# LVDS_IFC_DAC.net
KiCad netlist of a schematic drawn in Altium Designer
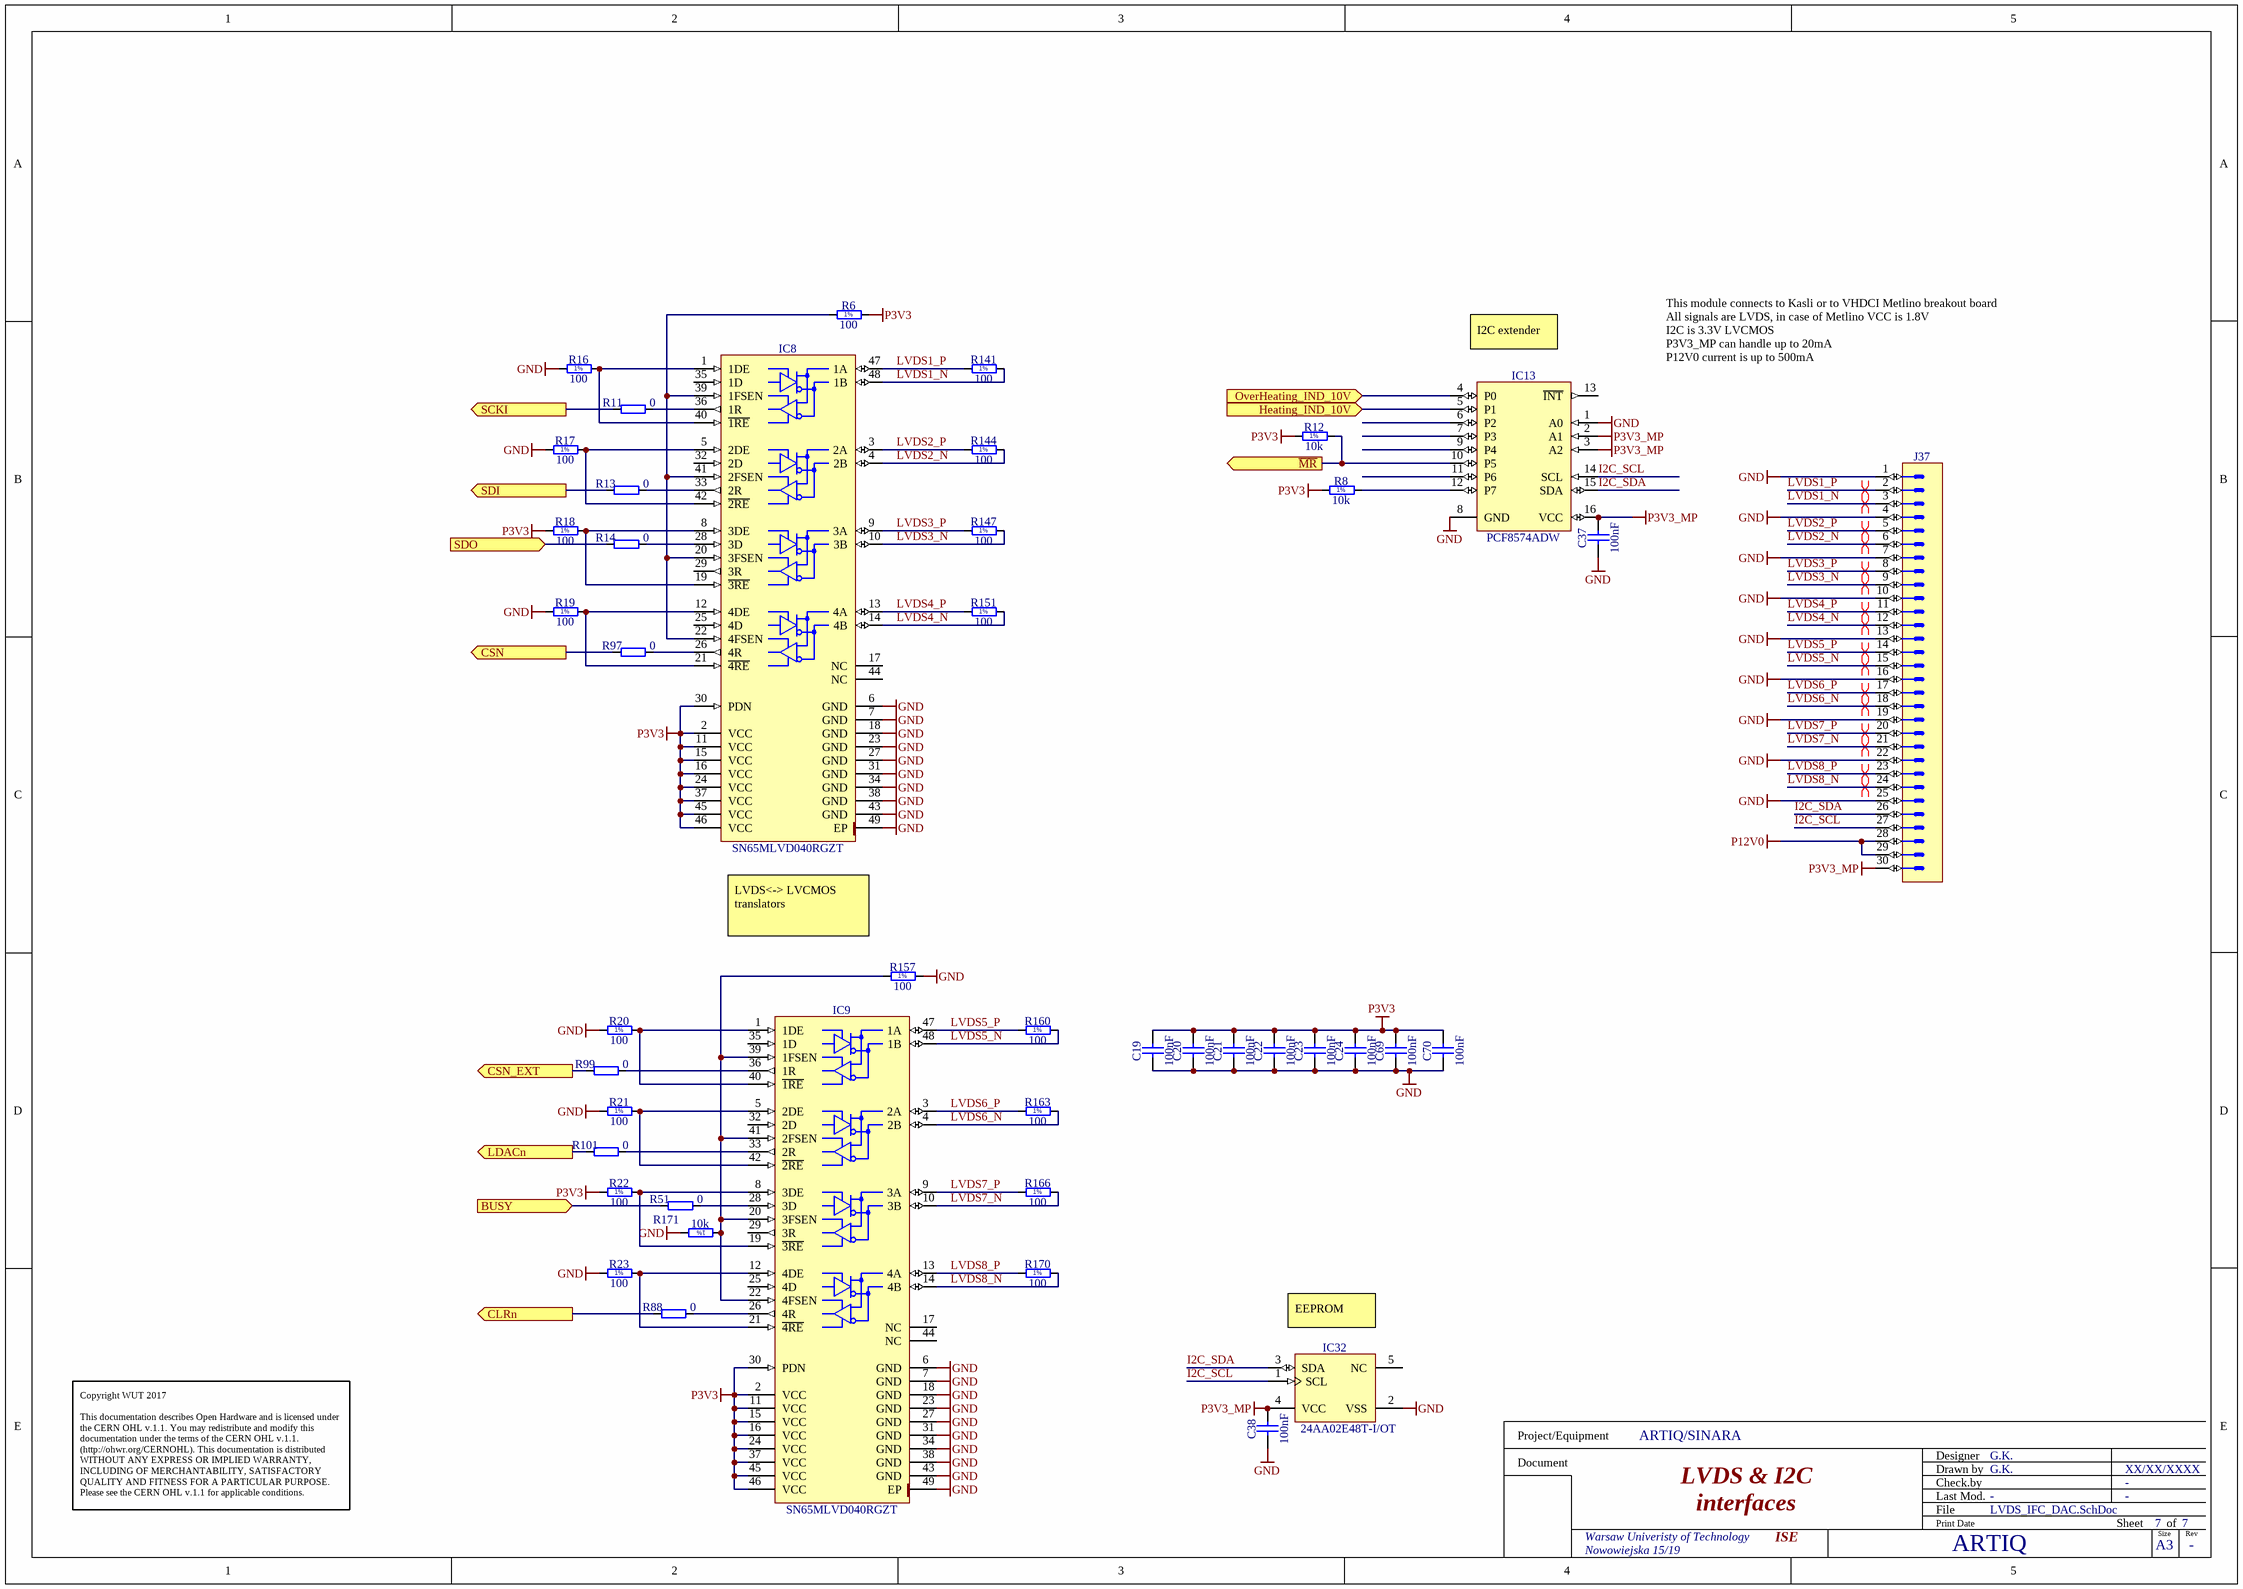
[diagram p0: LVDS_IFC_DAC.SchDoc]

(export (version "E")
  (design (tool "Eeschema 10.0.6"))
  (components
    (comp (ref "C19")
      (value "100nF")
      (footprint "CAPC1005X55N")
      (description "Non-polarised capacitor")
      (fields
        (field (name "PART NUMBER") "CC0402_100NF_16V_10%_X5R")
        (field (name "VOLTAGE") "16V")
        (field (name "AUTHOR") "CERN DEM JLC")
      )
      (libsource (lib "Capacitors") (part "Capacitor - non polarized"))
    )
    (comp (ref "C20")
      (value "100nF")
      (footprint "CAPC1005X55N")
      (description "Non-polarised capacitor")
      (fields
        (field (name "PART NUMBER") "CC0402_100NF_16V_10%_X5R")
        (field (name "VOLTAGE") "16V")
        (field (name "AUTHOR") "CERN DEM JLC")
      )
      (libsource (lib "Capacitors") (part "Capacitor - non polarized"))
    )
    (comp (ref "C21")
      (value "100nF")
      (footprint "CAPC1005X55N")
      (description "Non-polarised capacitor")
      (fields
        (field (name "PART NUMBER") "CC0402_100NF_16V_10%_X5R")
        (field (name "VOLTAGE") "16V")
        (field (name "AUTHOR") "CERN DEM JLC")
      )
      (libsource (lib "Capacitors") (part "Capacitor - non polarized"))
    )
    (comp (ref "C22")
      (value "100nF")
      (footprint "CAPC1005X55N")
      (description "Non-polarised capacitor")
      (fields
        (field (name "PART NUMBER") "CC0402_100NF_16V_10%_X5R")
        (field (name "VOLTAGE") "16V")
        (field (name "AUTHOR") "CERN DEM JLC")
      )
      (libsource (lib "Capacitors") (part "Capacitor - non polarized"))
    )
    (comp (ref "C23")
      (value "100nF")
      (footprint "CAPC1005X55N")
      (description "Non-polarised capacitor")
      (fields
        (field (name "PART NUMBER") "CC0402_100NF_16V_10%_X5R")
        (field (name "VOLTAGE") "16V")
        (field (name "AUTHOR") "CERN DEM JLC")
      )
      (libsource (lib "Capacitors") (part "Capacitor - non polarized"))
    )
    (comp (ref "C24")
      (value "100nF")
      (footprint "CAPC1005X55N")
      (description "Non-polarised capacitor")
      (fields
        (field (name "PART NUMBER") "CC0402_100NF_16V_10%_X5R")
        (field (name "VOLTAGE") "16V")
        (field (name "AUTHOR") "CERN DEM JLC")
      )
      (libsource (lib "Capacitors") (part "Capacitor - non polarized"))
    )
    (comp (ref "C37")
      (value "100nF")
      (footprint "CAPC1005X55N")
      (description "Non-polarised capacitor")
      (fields
        (field (name "PART NUMBER") "CC0402_100NF_16V_10%_X5R")
        (field (name "VOLTAGE") "16V")
        (field (name "AUTHOR") "CERN DEM JLC")
      )
      (libsource (lib "Capacitors") (part "Capacitor - non polarized"))
    )
    (comp (ref "C38")
      (value "100nF")
      (footprint "CAPC1005X55N")
      (description "Non-polarised capacitor")
      (fields
        (field (name "PART NUMBER") "CC0402_100NF_16V_10%_X5R")
        (field (name "VOLTAGE") "16V")
        (field (name "AUTHOR") "CERN DEM JLC")
      )
      (libsource (lib "Capacitors") (part "Capacitor - non polarized"))
    )
    (comp (ref "C69")
      (value "100nF")
      (footprint "CAPC1005X55N")
      (description "Non-polarised capacitor")
      (fields
        (field (name "PART NUMBER") "CC0402_100NF_16V_10%_X5R")
        (field (name "VOLTAGE") "16V")
        (field (name "AUTHOR") "CERN DEM JLC")
      )
      (libsource (lib "Capacitors") (part "Capacitor - non polarized"))
    )
    (comp (ref "C70")
      (value "100nF")
      (footprint "CAPC1005X55N")
      (description "Non-polarised capacitor")
      (fields
        (field (name "PART NUMBER") "CC0402_100NF_16V_10%_X5R")
        (field (name "VOLTAGE") "16V")
        (field (name "AUTHOR") "CERN DEM JLC")
      )
      (libsource (lib "Capacitors") (part "Capacitor - non polarized"))
    )
    (comp (ref "IC8")
      (value "SN65MLVD040RGZT")
      (footprint "QFN50P700X700X100-49N-S420")
      (description "4-Channel Half-Duplex M-LVDS Line Transceiver")
      (fields (field (name "MANUFACTURER") "TEXAS INSTRUMENTS") (field (name "AUTHOR") "CERN DEM JLC"))
      (libsource (lib "ICs And Semiconductors") (part "SN65MLVD040"))
    )
    (comp (ref "IC9")
      (value "SN65MLVD040RGZT")
      (footprint "QFN50P700X700X100-49N-S420")
      (description "4-Channel Half-Duplex M-LVDS Line Transceiver")
      (fields (field (name "MANUFACTURER") "TEXAS INSTRUMENTS") (field (name "AUTHOR") "CERN DEM JLC"))
      (libsource (lib "ICs And Semiconductors") (part "SN65MLVD040"))
    )
    (comp (ref "IC13")
      (value "PCF8574ADW")
      (footprint "SOIC127P1030X265-16N")
      (description "Remote 8-bit I/O Expander For I2C Bus")
      (fields (field (name "MANUFACTURER") "TEXAS INSTRUMENTS") (field (name "AUTHOR") "CERN DEM JLC"))
      (libsource (lib "ICs And Semiconductors") (part "PCF8574ADW"))
    )
    (comp (ref "IC32")
      (value "24AA02E48T-I/OT")
      (footprint "SOT95P280X145-5N")
      (description "1.7V-5.5V, 2K I2C Serial EEPROM With EUI-48 Node Identity")
      (fields (field (name "MANUFACTURER") "MICROCHIP TECHNOLOGY") (field (name "AUTHOR") "CERN DEM MR"))
      (libsource (lib "ICs And Semiconductors") (part "24AA02E48T-I/OT"))
    )
    (comp (ref "J37")
      (value "~")
      (footprint "3M_N2530-6002RB")
      (description "Connector 30 Male")
      (fields
        (field (name "PART NUMBER") "3M_N2530-6002RB")
        (field (name "MANUFACTURER") "3M")
        (field (name "AUTHOR") "CERN DEM JLC")
      )
      (libsource (lib "Connectors") (part "Connector 30 Male"))
    )
    (comp (ref "R6")
      (value "100")
      (footprint "RESC1005X40N")
      (description "Resistor - 1%")
      (fields
        (field (name "PART NUMBER") "R0402_100R_1%_0.1W_100PPM")
        (field (name "POWER") "0.1W")
        (field (name "AUTHOR") "CERN DEM JLC")
      )
      (libsource (lib "Resistors") (part "Resistor - 1%"))
    )
    (comp (ref "R8")
      (value "10k")
      (footprint "RESC1608X55N")
      (description "Resistor - 1%")
      (fields
        (field (name "PART NUMBER") "R0603_10K_1%_0.1W_100PPM")
        (field (name "POWER") "0.1W")
        (field (name "AUTHOR") "CERN DEM JLC")
      )
      (libsource (lib "Resistors") (part "Resistor - 1%"))
    )
    (comp (ref "R11")
      (value "0")
      (footprint "RESC1005X40N")
      (description "Resistor")
      (fields
        (field (name "PART NUMBER") "R0402_0R_JUMPER")
        (field (name "MANUFACTURER") "GENERIC")
        (field (name "AUTHOR") "CERN DEM JLC")
      )
      (libsource (lib "Resistors") (part "Resistor"))
    )
    (comp (ref "R12")
      (value "10k")
      (footprint "RESC1608X55N")
      (description "Resistor - 1%")
      (fields
        (field (name "PART NUMBER") "R0603_10K_1%_0.1W_100PPM")
        (field (name "POWER") "0.1W")
        (field (name "AUTHOR") "CERN DEM JLC")
      )
      (libsource (lib "Resistors") (part "Resistor - 1%"))
    )
    (comp (ref "R13")
      (value "0")
      (footprint "RESC1005X40N")
      (description "Resistor")
      (fields
        (field (name "PART NUMBER") "R0402_0R_JUMPER")
        (field (name "MANUFACTURER") "GENERIC")
        (field (name "AUTHOR") "CERN DEM JLC")
      )
      (libsource (lib "Resistors") (part "Resistor"))
    )
    (comp (ref "R14")
      (value "0")
      (footprint "RESC1005X40N")
      (description "Resistor")
      (fields
        (field (name "PART NUMBER") "R0402_0R_JUMPER")
        (field (name "MANUFACTURER") "GENERIC")
        (field (name "AUTHOR") "CERN DEM JLC")
      )
      (libsource (lib "Resistors") (part "Resistor"))
    )
    (comp (ref "R16")
      (value "100")
      (footprint "RESC1005X40N")
      (description "Resistor - 1%")
      (fields
        (field (name "PART NUMBER") "R0402_100R_1%_0.1W_100PPM")
        (field (name "POWER") "0.1W")
        (field (name "AUTHOR") "CERN DEM JLC")
      )
      (libsource (lib "Resistors") (part "Resistor - 1%"))
    )
    (comp (ref "R17")
      (value "100")
      (footprint "RESC1005X40N")
      (description "Resistor - 1%")
      (fields
        (field (name "PART NUMBER") "R0402_100R_1%_0.1W_100PPM")
        (field (name "POWER") "0.1W")
        (field (name "AUTHOR") "CERN DEM JLC")
      )
      (libsource (lib "Resistors") (part "Resistor - 1%"))
    )
    (comp (ref "R18")
      (value "100")
      (footprint "RESC1005X40N")
      (description "Resistor - 1%")
      (fields
        (field (name "PART NUMBER") "R0402_100R_1%_0.1W_100PPM")
        (field (name "POWER") "0.1W")
        (field (name "AUTHOR") "CERN DEM JLC")
      )
      (libsource (lib "Resistors") (part "Resistor - 1%"))
    )
    (comp (ref "R19")
      (value "100")
      (footprint "RESC1005X40N")
      (description "Resistor - 1%")
      (fields
        (field (name "PART NUMBER") "R0402_100R_1%_0.1W_100PPM")
        (field (name "POWER") "0.1W")
        (field (name "AUTHOR") "CERN DEM JLC")
      )
      (libsource (lib "Resistors") (part "Resistor - 1%"))
    )
    (comp (ref "R20")
      (value "100")
      (footprint "RESC1005X40N")
      (description "Resistor - 1%")
      (fields
        (field (name "PART NUMBER") "R0402_100R_1%_0.1W_100PPM")
        (field (name "POWER") "0.1W")
        (field (name "AUTHOR") "CERN DEM JLC")
      )
      (libsource (lib "Resistors") (part "Resistor - 1%"))
    )
    (comp (ref "R21")
      (value "100")
      (footprint "RESC1005X40N")
      (description "Resistor - 1%")
      (fields
        (field (name "PART NUMBER") "R0402_100R_1%_0.1W_100PPM")
        (field (name "POWER") "0.1W")
        (field (name "AUTHOR") "CERN DEM JLC")
      )
      (libsource (lib "Resistors") (part "Resistor - 1%"))
    )
    (comp (ref "R22")
      (value "100")
      (footprint "RESC1005X40N")
      (description "Resistor - 1%")
      (fields
        (field (name "PART NUMBER") "R0402_100R_1%_0.1W_100PPM")
        (field (name "POWER") "0.1W")
        (field (name "AUTHOR") "CERN DEM JLC")
      )
      (libsource (lib "Resistors") (part "Resistor - 1%"))
    )
    (comp (ref "R23")
      (value "100")
      (footprint "RESC1005X40N")
      (description "Resistor - 1%")
      (fields
        (field (name "PART NUMBER") "R0402_100R_1%_0.1W_100PPM")
        (field (name "POWER") "0.1W")
        (field (name "AUTHOR") "CERN DEM JLC")
      )
      (libsource (lib "Resistors") (part "Resistor - 1%"))
    )
    (comp (ref "R51")
      (value "0")
      (footprint "RESC1005X40N")
      (description "Resistor")
      (fields
        (field (name "PART NUMBER") "R0402_0R_JUMPER")
        (field (name "MANUFACTURER") "GENERIC")
        (field (name "AUTHOR") "CERN DEM JLC")
      )
      (libsource (lib "Resistors") (part "Resistor"))
    )
    (comp (ref "R88")
      (value "0")
      (footprint "RESC1005X40N")
      (description "Resistor")
      (fields
        (field (name "PART NUMBER") "R0402_0R_JUMPER")
        (field (name "MANUFACTURER") "GENERIC")
        (field (name "AUTHOR") "CERN DEM JLC")
      )
      (libsource (lib "Resistors") (part "Resistor"))
    )
    (comp (ref "R97")
      (value "0")
      (footprint "RESC1005X40N")
      (description "Resistor")
      (fields
        (field (name "PART NUMBER") "R0402_0R_JUMPER")
        (field (name "MANUFACTURER") "GENERIC")
        (field (name "AUTHOR") "CERN DEM JLC")
      )
      (libsource (lib "Resistors") (part "Resistor"))
    )
    (comp (ref "R99")
      (value "0")
      (footprint "RESC1005X40N")
      (description "Resistor")
      (fields
        (field (name "PART NUMBER") "R0402_0R_JUMPER")
        (field (name "MANUFACTURER") "GENERIC")
        (field (name "AUTHOR") "CERN DEM JLC")
      )
      (libsource (lib "Resistors") (part "Resistor"))
    )
    (comp (ref "R101")
      (value "0")
      (footprint "RESC1005X40N")
      (description "Resistor")
      (fields
        (field (name "PART NUMBER") "R0402_0R_JUMPER")
        (field (name "MANUFACTURER") "GENERIC")
        (field (name "AUTHOR") "CERN DEM JLC")
      )
      (libsource (lib "Resistors") (part "Resistor"))
    )
    (comp (ref "R141")
      (value "100")
      (footprint "RESC1005X40N")
      (description "Resistor - 1%")
      (fields
        (field (name "PART NUMBER") "R0402_100R_1%_0.1W_100PPM")
        (field (name "POWER") "0.1W")
        (field (name "AUTHOR") "CERN DEM JLC")
      )
      (libsource (lib "Resistors") (part "Resistor - 1%"))
    )
    (comp (ref "R144")
      (value "100")
      (footprint "RESC1005X40N")
      (description "Resistor - 1%")
      (fields
        (field (name "PART NUMBER") "R0402_100R_1%_0.1W_100PPM")
        (field (name "POWER") "0.1W")
        (field (name "AUTHOR") "CERN DEM JLC")
      )
      (libsource (lib "Resistors") (part "Resistor - 1%"))
    )
    (comp (ref "R147")
      (value "100")
      (footprint "RESC1005X40N")
      (description "Resistor - 1%")
      (fields
        (field (name "PART NUMBER") "R0402_100R_1%_0.1W_100PPM")
        (field (name "POWER") "0.1W")
        (field (name "AUTHOR") "CERN DEM JLC")
      )
      (libsource (lib "Resistors") (part "Resistor - 1%"))
    )
    (comp (ref "R151")
      (value "100")
      (footprint "RESC1005X40N")
      (description "Resistor - 1%")
      (fields
        (field (name "PART NUMBER") "R0402_100R_1%_0.1W_100PPM")
        (field (name "POWER") "0.1W")
        (field (name "AUTHOR") "CERN DEM JLC")
      )
      (libsource (lib "Resistors") (part "Resistor - 1%"))
    )
    (comp (ref "R157")
      (value "100")
      (footprint "RESC1005X40N")
      (description "Resistor - 1%")
      (fields
        (field (name "PART NUMBER") "R0402_100R_1%_0.1W_100PPM")
        (field (name "POWER") "0.1W")
        (field (name "AUTHOR") "CERN DEM JLC")
      )
      (libsource (lib "Resistors") (part "Resistor - 1%"))
    )
    (comp (ref "R160")
      (value "100")
      (footprint "RESC1005X40N")
      (description "Resistor - 1%")
      (fields
        (field (name "PART NUMBER") "R0402_100R_1%_0.1W_100PPM")
        (field (name "POWER") "0.1W")
        (field (name "AUTHOR") "CERN DEM JLC")
      )
      (libsource (lib "Resistors") (part "Resistor - 1%"))
    )
    (comp (ref "R163")
      (value "100")
      (footprint "RESC1005X40N")
      (description "Resistor - 1%")
      (fields
        (field (name "PART NUMBER") "R0402_100R_1%_0.1W_100PPM")
        (field (name "POWER") "0.1W")
        (field (name "AUTHOR") "CERN DEM JLC")
      )
      (libsource (lib "Resistors") (part "Resistor - 1%"))
    )
    (comp (ref "R166")
      (value "100")
      (footprint "RESC1005X40N")
      (description "Resistor - 1%")
      (fields
        (field (name "PART NUMBER") "R0402_100R_1%_0.1W_100PPM")
        (field (name "POWER") "0.1W")
        (field (name "AUTHOR") "CERN DEM JLC")
      )
      (libsource (lib "Resistors") (part "Resistor - 1%"))
    )
    (comp (ref "R170")
      (value "100")
      (footprint "RESC1005X40N")
      (description "Resistor - 1%")
      (fields
        (field (name "PART NUMBER") "R0402_100R_1%_0.1W_100PPM")
        (field (name "POWER") "0.1W")
        (field (name "AUTHOR") "CERN DEM JLC")
      )
      (libsource (lib "Resistors") (part "Resistor - 1%"))
    )
    (comp (ref "R171")
      (value "10k")
      (footprint "RESC1005X40N")
      (description "Resistor - 1%")
      (fields
        (field (name "PART NUMBER") "R0402_10K_1%_0.0625W_100PPM")
        (field (name "POWER") "0.0625W")
        (field (name "AUTHOR") "CERN DEM JLC")
      )
      (libsource (lib "Resistors") (part "Resistor - 1%"))
    )
  )
  (nets
    (net (code "1") (name "/BUSY") (class "Default")
      (node (ref "R51") (pin "1") (pinfunction "1_1") (pintype "passive"))
    )
    (net (code "2") (name "/CLRn") (class "Default")
      (node (ref "R88") (pin "1") (pinfunction "1_1") (pintype "passive"))
    )
    (net (code "3") (name "/CSN") (class "Default")
      (node (ref "R97") (pin "1") (pinfunction "1_1") (pintype "passive"))
    )
    (net (code "4") (name "/CSN_EXT") (class "Default")
      (node (ref "R99") (pin "1") (pinfunction "1_1") (pintype "passive"))
    )
    (net (code "5") (name "/Heating_IND_10V") (class "Default")
      (node (ref "IC13") (pin "5") (pinfunction "P1_5") (pintype "bidirectional"))
    )
    (net (code "6") (name "/I2C_SCL") (class "Default")
      (node (ref "IC13") (pin "14") (pinfunction "SCL_14") (pintype "input"))
      (node (ref "IC32") (pin "1") (pinfunction "SCL_1") (pintype "input"))
      (node (ref "J37") (pin "27") (pinfunction "27_27") (pintype "bidirectional"))
    )
    (net (code "7") (name "/I2C_SDA") (class "Default")
      (node (ref "IC13") (pin "15") (pinfunction "SDA_15") (pintype "bidirectional"))
      (node (ref "IC32") (pin "3") (pinfunction "SDA_3") (pintype "bidirectional"))
      (node (ref "J37") (pin "26") (pinfunction "26_26") (pintype "bidirectional"))
    )
    (net (code "8") (name "/LDACn") (class "Default")
      (node (ref "R101") (pin "1") (pinfunction "1_1") (pintype "passive"))
    )
    (net (code "9") (name "/LVDS1_N") (class "Default")
      (node (ref "IC8") (pin "48") (pinfunction "1B_48") (pintype "bidirectional"))
      (node (ref "J37") (pin "3") (pinfunction "3_3") (pintype "bidirectional"))
      (node (ref "R141") (pin "2") (pinfunction "2_2") (pintype "passive"))
    )
    (net (code "10") (name "/LVDS1_P") (class "Default")
      (node (ref "IC8") (pin "47") (pinfunction "1A_47") (pintype "bidirectional"))
      (node (ref "J37") (pin "2") (pinfunction "2_2") (pintype "bidirectional"))
      (node (ref "R141") (pin "1") (pinfunction "1_1") (pintype "passive"))
    )
    (net (code "11") (name "/LVDS2_N") (class "Default")
      (node (ref "IC8") (pin "4") (pinfunction "2B_4") (pintype "bidirectional"))
      (node (ref "J37") (pin "6") (pinfunction "6_6") (pintype "bidirectional"))
      (node (ref "R144") (pin "2") (pinfunction "2_2") (pintype "passive"))
    )
    (net (code "12") (name "/LVDS2_P") (class "Default")
      (node (ref "IC8") (pin "3") (pinfunction "2A_3") (pintype "bidirectional"))
      (node (ref "J37") (pin "5") (pinfunction "5_5") (pintype "bidirectional"))
      (node (ref "R144") (pin "1") (pinfunction "1_1") (pintype "passive"))
    )
    (net (code "13") (name "/LVDS3_N") (class "Default")
      (node (ref "IC8") (pin "10") (pinfunction "3B_10") (pintype "bidirectional"))
      (node (ref "J37") (pin "9") (pinfunction "9_9") (pintype "bidirectional"))
      (node (ref "R147") (pin "2") (pinfunction "2_2") (pintype "passive"))
    )
    (net (code "14") (name "/LVDS3_P") (class "Default")
      (node (ref "IC8") (pin "9") (pinfunction "3A_9") (pintype "bidirectional"))
      (node (ref "J37") (pin "8") (pinfunction "8_8") (pintype "bidirectional"))
      (node (ref "R147") (pin "1") (pinfunction "1_1") (pintype "passive"))
    )
    (net (code "15") (name "/LVDS4_N") (class "Default")
      (node (ref "IC8") (pin "14") (pinfunction "4B_14") (pintype "bidirectional"))
      (node (ref "J37") (pin "12") (pinfunction "12_12") (pintype "bidirectional"))
      (node (ref "R151") (pin "2") (pinfunction "2_2") (pintype "passive"))
    )
    (net (code "16") (name "/LVDS4_P") (class "Default")
      (node (ref "IC8") (pin "13") (pinfunction "4A_13") (pintype "bidirectional"))
      (node (ref "J37") (pin "11") (pinfunction "11_11") (pintype "bidirectional"))
      (node (ref "R151") (pin "1") (pinfunction "1_1") (pintype "passive"))
    )
    (net (code "17") (name "/LVDS5_N") (class "Default")
      (node (ref "IC9") (pin "48") (pinfunction "1B_48") (pintype "bidirectional"))
      (node (ref "J37") (pin "15") (pinfunction "15_15") (pintype "bidirectional"))
      (node (ref "R160") (pin "2") (pinfunction "2_2") (pintype "passive"))
    )
    (net (code "18") (name "/LVDS5_P") (class "Default")
      (node (ref "IC9") (pin "47") (pinfunction "1A_47") (pintype "bidirectional"))
      (node (ref "J37") (pin "14") (pinfunction "14_14") (pintype "bidirectional"))
      (node (ref "R160") (pin "1") (pinfunction "1_1") (pintype "passive"))
    )
    (net (code "19") (name "/LVDS6_N") (class "Default")
      (node (ref "IC9") (pin "4") (pinfunction "2B_4") (pintype "bidirectional"))
      (node (ref "J37") (pin "18") (pinfunction "18_18") (pintype "bidirectional"))
      (node (ref "R163") (pin "2") (pinfunction "2_2") (pintype "passive"))
    )
    (net (code "20") (name "/LVDS6_P") (class "Default")
      (node (ref "IC9") (pin "3") (pinfunction "2A_3") (pintype "bidirectional"))
      (node (ref "J37") (pin "17") (pinfunction "17_17") (pintype "bidirectional"))
      (node (ref "R163") (pin "1") (pinfunction "1_1") (pintype "passive"))
    )
    (net (code "21") (name "/LVDS7_N") (class "Default")
      (node (ref "IC9") (pin "10") (pinfunction "3B_10") (pintype "bidirectional"))
      (node (ref "J37") (pin "21") (pinfunction "21_21") (pintype "bidirectional"))
      (node (ref "R166") (pin "2") (pinfunction "2_2") (pintype "passive"))
    )
    (net (code "22") (name "/LVDS7_P") (class "Default")
      (node (ref "IC9") (pin "9") (pinfunction "3A_9") (pintype "bidirectional"))
      (node (ref "J37") (pin "20") (pinfunction "20_20") (pintype "bidirectional"))
      (node (ref "R166") (pin "1") (pinfunction "1_1") (pintype "passive"))
    )
    (net (code "23") (name "/LVDS8_N") (class "Default")
      (node (ref "IC9") (pin "14") (pinfunction "4B_14") (pintype "bidirectional"))
      (node (ref "J37") (pin "24") (pinfunction "24_24") (pintype "bidirectional"))
      (node (ref "R170") (pin "2") (pinfunction "2_2") (pintype "passive"))
    )
    (net (code "24") (name "/LVDS8_P") (class "Default")
      (node (ref "IC9") (pin "13") (pinfunction "4A_13") (pintype "bidirectional"))
      (node (ref "J37") (pin "23") (pinfunction "23_23") (pintype "bidirectional"))
      (node (ref "R170") (pin "1") (pinfunction "1_1") (pintype "passive"))
    )
    (net (code "25") (name "/OverHeating_IND_10V") (class "Default")
      (node (ref "IC13") (pin "4") (pinfunction "P0_4") (pintype "bidirectional"))
    )
    (net (code "26") (name "/SCKI") (class "Default")
      (node (ref "R11") (pin "1") (pinfunction "1_1") (pintype "passive"))
    )
    (net (code "27") (name "/SDI") (class "Default")
      (node (ref "R13") (pin "1") (pinfunction "1_1") (pintype "passive"))
    )
    (net (code "28") (name "/SDO") (class "Default")
      (node (ref "R14") (pin "1") (pinfunction "1_1") (pintype "passive"))
    )
    (net (code "29") (name "/~{MR}") (class "Default")
      (node (ref "IC13") (pin "10") (pinfunction "P5_10") (pintype "bidirectional"))
      (node (ref "R12") (pin "2") (pinfunction "2_2") (pintype "passive"))
    )
    (net (code "30") (name "GND") (class "Default")
      (node (ref "C19") (pin "1") (pinfunction "1_1") (pintype "passive"))
      (node (ref "C20") (pin "1") (pinfunction "1_1") (pintype "passive"))
      (node (ref "C21") (pin "1") (pinfunction "1_1") (pintype "passive"))
      (node (ref "C22") (pin "1") (pinfunction "1_1") (pintype "passive"))
      (node (ref "C23") (pin "1") (pinfunction "1_1") (pintype "passive"))
      (node (ref "C24") (pin "1") (pinfunction "1_1") (pintype "passive"))
      (node (ref "C37") (pin "1") (pinfunction "1_1") (pintype "passive"))
      (node (ref "C38") (pin "1") (pinfunction "1_1") (pintype "passive"))
      (node (ref "C69") (pin "1") (pinfunction "1_1") (pintype "passive"))
      (node (ref "C70") (pin "1") (pinfunction "1_1") (pintype "passive"))
      (node (ref "IC13") (pin "1") (pinfunction "A0_1") (pintype "input"))
      (node (ref "IC13") (pin "8") (pinfunction "GND_8") (pintype "power_in"))
      (node (ref "IC32") (pin "2") (pinfunction "VSS_2") (pintype "power_in"))
      (node (ref "IC8") (pin "18") (pinfunction "GND_18") (pintype "power_in"))
      (node (ref "IC8") (pin "23") (pinfunction "GND_23") (pintype "power_in"))
      (node (ref "IC8") (pin "27") (pinfunction "GND_27") (pintype "power_in"))
      (node (ref "IC8") (pin "31") (pinfunction "GND_31") (pintype "power_in"))
      (node (ref "IC8") (pin "34") (pinfunction "GND_34") (pintype "power_in"))
      (node (ref "IC8") (pin "38") (pinfunction "GND_38") (pintype "power_in"))
      (node (ref "IC8") (pin "43") (pinfunction "GND_43") (pintype "power_in"))
      (node (ref "IC8") (pin "49") (pinfunction "EP_49") (pintype "power_in"))
      (node (ref "IC8") (pin "6") (pinfunction "GND_6") (pintype "power_in"))
      (node (ref "IC8") (pin "7") (pinfunction "GND_7") (pintype "power_in"))
      (node (ref "IC9") (pin "18") (pinfunction "GND_18") (pintype "power_in"))
      (node (ref "IC9") (pin "23") (pinfunction "GND_23") (pintype "power_in"))
      (node (ref "IC9") (pin "27") (pinfunction "GND_27") (pintype "power_in"))
      (node (ref "IC9") (pin "31") (pinfunction "GND_31") (pintype "power_in"))
      (node (ref "IC9") (pin "34") (pinfunction "GND_34") (pintype "power_in"))
      (node (ref "IC9") (pin "38") (pinfunction "GND_38") (pintype "power_in"))
      (node (ref "IC9") (pin "43") (pinfunction "GND_43") (pintype "power_in"))
      (node (ref "IC9") (pin "49") (pinfunction "EP_49") (pintype "power_in"))
      (node (ref "IC9") (pin "6") (pinfunction "GND_6") (pintype "power_in"))
      (node (ref "IC9") (pin "7") (pinfunction "GND_7") (pintype "power_in"))
      (node (ref "J37") (pin "1") (pinfunction "1_1") (pintype "bidirectional"))
      (node (ref "J37") (pin "10") (pinfunction "10_10") (pintype "bidirectional"))
      (node (ref "J37") (pin "13") (pinfunction "13_13") (pintype "bidirectional"))
      (node (ref "J37") (pin "16") (pinfunction "16_16") (pintype "bidirectional"))
      (node (ref "J37") (pin "19") (pinfunction "19_19") (pintype "bidirectional"))
      (node (ref "J37") (pin "22") (pinfunction "22_22") (pintype "bidirectional"))
      (node (ref "J37") (pin "25") (pinfunction "25_25") (pintype "bidirectional"))
      (node (ref "J37") (pin "4") (pinfunction "4_4") (pintype "bidirectional"))
      (node (ref "J37") (pin "7") (pinfunction "7_7") (pintype "bidirectional"))
      (node (ref "R157") (pin "2") (pinfunction "2_2") (pintype "passive"))
      (node (ref "R16") (pin "1") (pinfunction "1_1") (pintype "passive"))
      (node (ref "R17") (pin "1") (pinfunction "1_1") (pintype "passive"))
      (node (ref "R171") (pin "2") (pinfunction "2_2") (pintype "passive"))
      (node (ref "R19") (pin "1") (pinfunction "1_1") (pintype "passive"))
      (node (ref "R20") (pin "1") (pinfunction "1_1") (pintype "passive"))
      (node (ref "R21") (pin "1") (pinfunction "1_1") (pintype "passive"))
      (node (ref "R23") (pin "1") (pinfunction "1_1") (pintype "passive"))
    )
    (net (code "31") (name "Net-(IC8-1DE)") (class "Default")
      (node (ref "IC8") (pin "1") (pinfunction "1DE_1") (pintype "input"))
      (node (ref "IC8") (pin "40") (pinfunction "~{1RE}_40") (pintype "input"))
      (node (ref "R16") (pin "2") (pinfunction "2_2") (pintype "passive"))
    )
    (net (code "32") (name "Net-(IC8-1FSEN)") (class "Default")
      (node (ref "IC8") (pin "20") (pinfunction "3FSEN_20") (pintype "input"))
      (node (ref "IC8") (pin "22") (pinfunction "4FSEN_22") (pintype "input"))
      (node (ref "IC8") (pin "39") (pinfunction "1FSEN_39") (pintype "input"))
      (node (ref "IC8") (pin "41") (pinfunction "2FSEN_41") (pintype "input"))
      (node (ref "R6") (pin "1") (pinfunction "1_1") (pintype "passive"))
    )
    (net (code "33") (name "Net-(IC8-1R)") (class "Default")
      (node (ref "IC8") (pin "36") (pinfunction "1R_36") (pintype "output"))
      (node (ref "R11") (pin "2") (pinfunction "2_2") (pintype "passive"))
    )
    (net (code "34") (name "Net-(IC8-2DE)") (class "Default")
      (node (ref "IC8") (pin "42") (pinfunction "~{2RE}_42") (pintype "input"))
      (node (ref "IC8") (pin "5") (pinfunction "2DE_5") (pintype "input"))
      (node (ref "R17") (pin "2") (pinfunction "2_2") (pintype "passive"))
    )
    (net (code "35") (name "Net-(IC8-2R)") (class "Default")
      (node (ref "IC8") (pin "33") (pinfunction "2R_33") (pintype "output"))
      (node (ref "R13") (pin "2") (pinfunction "2_2") (pintype "passive"))
    )
    (net (code "36") (name "Net-(IC8-3D)") (class "Default")
      (node (ref "IC8") (pin "28") (pinfunction "3D_28") (pintype "input"))
      (node (ref "R14") (pin "2") (pinfunction "2_2") (pintype "passive"))
    )
    (net (code "37") (name "Net-(IC8-3DE)") (class "Default")
      (node (ref "IC8") (pin "19") (pinfunction "~{3RE}_19") (pintype "input"))
      (node (ref "IC8") (pin "8") (pinfunction "3DE_8") (pintype "input"))
      (node (ref "R18") (pin "2") (pinfunction "2_2") (pintype "passive"))
    )
    (net (code "38") (name "Net-(IC8-4DE)") (class "Default")
      (node (ref "IC8") (pin "12") (pinfunction "4DE_12") (pintype "input"))
      (node (ref "IC8") (pin "21") (pinfunction "~{4RE}_21") (pintype "input"))
      (node (ref "R19") (pin "2") (pinfunction "2_2") (pintype "passive"))
    )
    (net (code "39") (name "Net-(IC8-4R)") (class "Default")
      (node (ref "IC8") (pin "26") (pinfunction "4R_26") (pintype "output"))
      (node (ref "R97") (pin "2") (pinfunction "2_2") (pintype "passive"))
    )
    (net (code "40") (name "Net-(IC9-1DE)") (class "Default")
      (node (ref "IC9") (pin "1") (pinfunction "1DE_1") (pintype "input"))
      (node (ref "IC9") (pin "40") (pinfunction "~{1RE}_40") (pintype "input"))
      (node (ref "R20") (pin "2") (pinfunction "2_2") (pintype "passive"))
    )
    (net (code "41") (name "Net-(IC9-1FSEN)") (class "Default")
      (node (ref "IC9") (pin "20") (pinfunction "3FSEN_20") (pintype "input"))
      (node (ref "IC9") (pin "22") (pinfunction "4FSEN_22") (pintype "input"))
      (node (ref "IC9") (pin "39") (pinfunction "1FSEN_39") (pintype "input"))
      (node (ref "IC9") (pin "41") (pinfunction "2FSEN_41") (pintype "input"))
      (node (ref "R157") (pin "1") (pinfunction "1_1") (pintype "passive"))
      (node (ref "R171") (pin "1") (pinfunction "1_1") (pintype "passive"))
    )
    (net (code "42") (name "Net-(IC9-1R)") (class "Default")
      (node (ref "IC9") (pin "36") (pinfunction "1R_36") (pintype "output"))
      (node (ref "R99") (pin "2") (pinfunction "2_2") (pintype "passive"))
    )
    (net (code "43") (name "Net-(IC9-2DE)") (class "Default")
      (node (ref "IC9") (pin "42") (pinfunction "~{2RE}_42") (pintype "input"))
      (node (ref "IC9") (pin "5") (pinfunction "2DE_5") (pintype "input"))
      (node (ref "R21") (pin "2") (pinfunction "2_2") (pintype "passive"))
    )
    (net (code "44") (name "Net-(IC9-2R)") (class "Default")
      (node (ref "IC9") (pin "33") (pinfunction "2R_33") (pintype "output"))
      (node (ref "R101") (pin "2") (pinfunction "2_2") (pintype "passive"))
    )
    (net (code "45") (name "Net-(IC9-3D)") (class "Default")
      (node (ref "IC9") (pin "28") (pinfunction "3D_28") (pintype "input"))
      (node (ref "R51") (pin "2") (pinfunction "2_2") (pintype "passive"))
    )
    (net (code "46") (name "Net-(IC9-3DE)") (class "Default")
      (node (ref "IC9") (pin "19") (pinfunction "~{3RE}_19") (pintype "input"))
      (node (ref "IC9") (pin "8") (pinfunction "3DE_8") (pintype "input"))
      (node (ref "R22") (pin "2") (pinfunction "2_2") (pintype "passive"))
    )
    (net (code "47") (name "Net-(IC9-4DE)") (class "Default")
      (node (ref "IC9") (pin "12") (pinfunction "4DE_12") (pintype "input"))
      (node (ref "IC9") (pin "21") (pinfunction "~{4RE}_21") (pintype "input"))
      (node (ref "R23") (pin "2") (pinfunction "2_2") (pintype "passive"))
    )
    (net (code "48") (name "Net-(IC9-4R)") (class "Default")
      (node (ref "IC9") (pin "26") (pinfunction "4R_26") (pintype "output"))
      (node (ref "R88") (pin "2") (pinfunction "2_2") (pintype "passive"))
    )
    (net (code "49") (name "Net-(IC13-P7)") (class "Default")
      (node (ref "IC13") (pin "12") (pinfunction "P7_12") (pintype "bidirectional"))
      (node (ref "R8") (pin "2") (pinfunction "2_2") (pintype "passive"))
    )
    (net (code "50") (name "P3V3") (class "Default")
      (node (ref "C19") (pin "2") (pinfunction "2_2") (pintype "passive"))
      (node (ref "C20") (pin "2") (pinfunction "2_2") (pintype "passive"))
      (node (ref "C21") (pin "2") (pinfunction "2_2") (pintype "passive"))
      (node (ref "C22") (pin "2") (pinfunction "2_2") (pintype "passive"))
      (node (ref "C23") (pin "2") (pinfunction "2_2") (pintype "passive"))
      (node (ref "C24") (pin "2") (pinfunction "2_2") (pintype "passive"))
      (node (ref "C69") (pin "2") (pinfunction "2_2") (pintype "passive"))
      (node (ref "C70") (pin "2") (pinfunction "2_2") (pintype "passive"))
      (node (ref "IC8") (pin "11") (pinfunction "VCC_11") (pintype "power_in"))
      (node (ref "IC8") (pin "15") (pinfunction "VCC_15") (pintype "power_in"))
      (node (ref "IC8") (pin "16") (pinfunction "VCC_16") (pintype "power_in"))
      (node (ref "IC8") (pin "2") (pinfunction "VCC_2") (pintype "power_in"))
      (node (ref "IC8") (pin "24") (pinfunction "VCC_24") (pintype "power_in"))
      (node (ref "IC8") (pin "30") (pinfunction "PDN_30") (pintype "input"))
      (node (ref "IC8") (pin "37") (pinfunction "VCC_37") (pintype "power_in"))
      (node (ref "IC8") (pin "45") (pinfunction "VCC_45") (pintype "power_in"))
      (node (ref "IC8") (pin "46") (pinfunction "VCC_46") (pintype "power_in"))
      (node (ref "IC9") (pin "11") (pinfunction "VCC_11") (pintype "power_in"))
      (node (ref "IC9") (pin "15") (pinfunction "VCC_15") (pintype "power_in"))
      (node (ref "IC9") (pin "16") (pinfunction "VCC_16") (pintype "power_in"))
      (node (ref "IC9") (pin "2") (pinfunction "VCC_2") (pintype "power_in"))
      (node (ref "IC9") (pin "24") (pinfunction "VCC_24") (pintype "power_in"))
      (node (ref "IC9") (pin "30") (pinfunction "PDN_30") (pintype "input"))
      (node (ref "IC9") (pin "37") (pinfunction "VCC_37") (pintype "power_in"))
      (node (ref "IC9") (pin "45") (pinfunction "VCC_45") (pintype "power_in"))
      (node (ref "IC9") (pin "46") (pinfunction "VCC_46") (pintype "power_in"))
      (node (ref "R12") (pin "1") (pinfunction "1_1") (pintype "passive"))
      (node (ref "R18") (pin "1") (pinfunction "1_1") (pintype "passive"))
      (node (ref "R22") (pin "1") (pinfunction "1_1") (pintype "passive"))
      (node (ref "R6") (pin "2") (pinfunction "2_2") (pintype "passive"))
      (node (ref "R8") (pin "1") (pinfunction "1_1") (pintype "passive"))
    )
    (net (code "51") (name "P3V3_MP") (class "Default")
      (node (ref "C37") (pin "2") (pinfunction "2_2") (pintype "passive"))
      (node (ref "C38") (pin "2") (pinfunction "2_2") (pintype "passive"))
      (node (ref "IC13") (pin "16") (pinfunction "VCC_16") (pintype "bidirectional"))
      (node (ref "IC13") (pin "2") (pinfunction "A1_2") (pintype "input"))
      (node (ref "IC13") (pin "3") (pinfunction "A2_3") (pintype "input"))
      (node (ref "IC32") (pin "4") (pinfunction "VCC_4") (pintype "power_in"))
      (node (ref "J37") (pin "30") (pinfunction "30_30") (pintype "bidirectional"))
    )
    (net (code "52") (name "P12V0") (class "Default")
      (node (ref "J37") (pin "28") (pinfunction "28_28") (pintype "bidirectional"))
      (node (ref "J37") (pin "29") (pinfunction "29_29") (pintype "bidirectional"))
    )
    (net (code "53") (name "unconnected-(IC8-1D-Pad35)") (class "Default")
      (node (ref "IC8") (pin "35") (pinfunction "1D_35") (pintype "input"))
    )
    (net (code "54") (name "unconnected-(IC8-2D-Pad32)") (class "Default")
      (node (ref "IC8") (pin "32") (pinfunction "2D_32") (pintype "input"))
    )
    (net (code "55") (name "unconnected-(IC8-3R-Pad29)") (class "Default")
      (node (ref "IC8") (pin "29") (pinfunction "3R_29") (pintype "output"))
    )
    (net (code "56") (name "unconnected-(IC8-4D-Pad25)") (class "Default")
      (node (ref "IC8") (pin "25") (pinfunction "4D_25") (pintype "input"))
    )
    (net (code "57") (name "unconnected-(IC8-NC-Pad17)") (class "Default")
      (node (ref "IC8") (pin "17") (pinfunction "NC_17") (pintype "passive"))
    )
    (net (code "58") (name "unconnected-(IC8-NC-Pad44)") (class "Default")
      (node (ref "IC8") (pin "44") (pinfunction "NC_44") (pintype "passive"))
    )
    (net (code "59") (name "unconnected-(IC9-1D-Pad35)") (class "Default")
      (node (ref "IC9") (pin "35") (pinfunction "1D_35") (pintype "input"))
    )
    (net (code "60") (name "unconnected-(IC9-2D-Pad32)") (class "Default")
      (node (ref "IC9") (pin "32") (pinfunction "2D_32") (pintype "input"))
    )
    (net (code "61") (name "unconnected-(IC9-3R-Pad29)") (class "Default")
      (node (ref "IC9") (pin "29") (pinfunction "3R_29") (pintype "output"))
    )
    (net (code "62") (name "unconnected-(IC9-4D-Pad25)") (class "Default")
      (node (ref "IC9") (pin "25") (pinfunction "4D_25") (pintype "input"))
    )
    (net (code "63") (name "unconnected-(IC9-NC-Pad17)") (class "Default")
      (node (ref "IC9") (pin "17") (pinfunction "NC_17") (pintype "passive"))
    )
    (net (code "64") (name "unconnected-(IC9-NC-Pad44)") (class "Default")
      (node (ref "IC9") (pin "44") (pinfunction "NC_44") (pintype "passive"))
    )
    (net (code "65") (name "unconnected-(IC13-P2-Pad6)") (class "Default")
      (node (ref "IC13") (pin "6") (pinfunction "P2_6") (pintype "bidirectional"))
    )
    (net (code "66") (name "unconnected-(IC13-P3-Pad7)") (class "Default")
      (node (ref "IC13") (pin "7") (pinfunction "P3_7") (pintype "bidirectional"))
    )
    (net (code "67") (name "unconnected-(IC13-P4-Pad9)") (class "Default")
      (node (ref "IC13") (pin "9") (pinfunction "P4_9") (pintype "bidirectional"))
    )
    (net (code "68") (name "unconnected-(IC13-P6-Pad11)") (class "Default")
      (node (ref "IC13") (pin "11") (pinfunction "P6_11") (pintype "bidirectional"))
    )
    (net (code "69") (name "unconnected-(IC13-~{INT}-Pad13)") (class "Default")
      (node (ref "IC13") (pin "13") (pinfunction "~{INT}_13") (pintype "output"))
    )
    (net (code "70") (name "unconnected-(IC32-NC-Pad5)") (class "Default")
      (node (ref "IC32") (pin "5") (pinfunction "NC_5") (pintype "passive"))
    )
  )
)
